# Controller.net
KiCad netlist of a schematic drawn in EAGLE
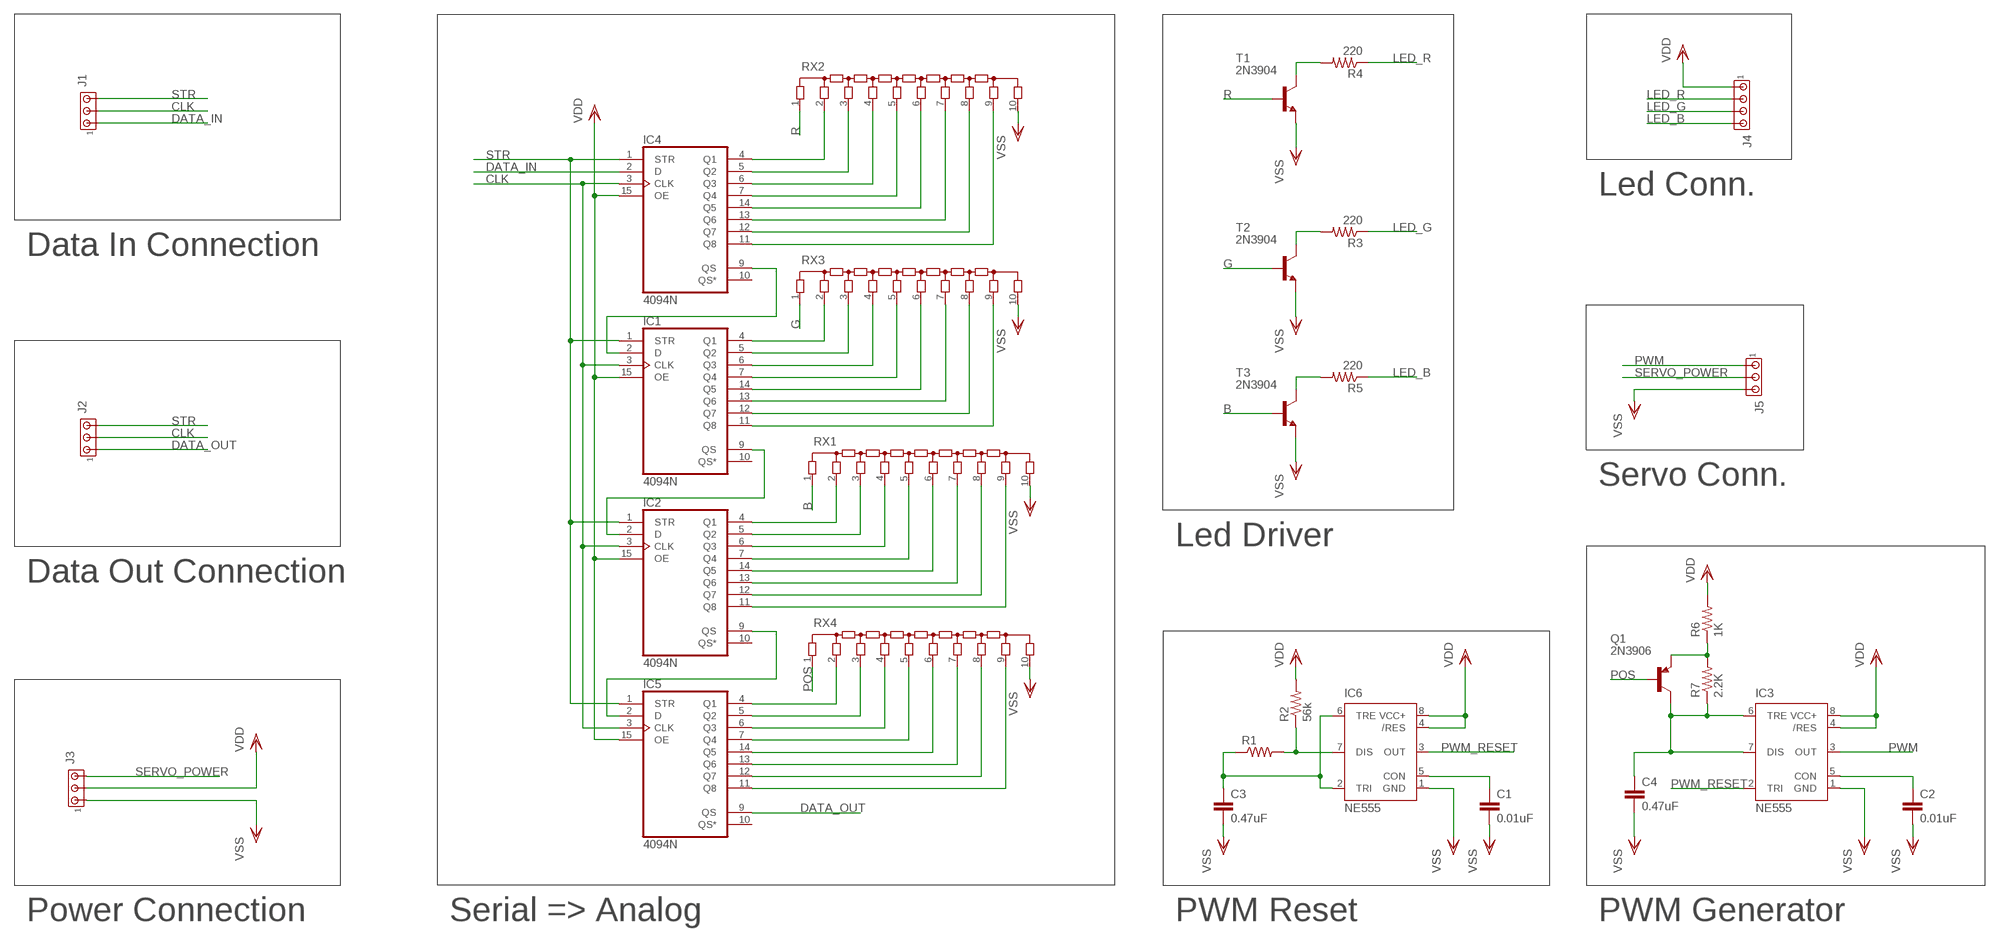
[diagram p0: schematic, sheet 1]

(export (version "E")
  (design (tool "Eeschema 10.0.6"))
  (components
    (comp (ref "C1")
      (value "0.01uF")
      (footprint "eagle-import:C5B2.5")
      (libsource (lib "eagle-import") (part "C5/2.5"))
    )
    (comp (ref "C2")
      (value "0.01uF")
      (footprint "eagle-import:C5B2.5")
      (libsource (lib "eagle-import") (part "C5/2.5"))
    )
    (comp (ref "C3")
      (value "0.47uF")
      (footprint "eagle-import:C5B2.5")
      (libsource (lib "eagle-import") (part "C5/2.5"))
    )
    (comp (ref "C4")
      (value "0.47uF")
      (footprint "eagle-import:C5B2.5")
      (libsource (lib "eagle-import") (part "C5/2.5"))
    )
    (comp (ref "IC1")
      (value "4094N")
      (footprint "eagle-import:DIL16")
      (libsource (lib "eagle-import") (part "4094N"))
    )
    (comp (ref "IC2")
      (value "4094N")
      (footprint "eagle-import:DIL16")
      (libsource (lib "eagle-import") (part "4094N"))
    )
    (comp (ref "IC3")
      (value "NE555")
      (footprint "eagle-import:DIL-08")
      (fields (field (name "MF") "Arrow Electronics") (field (name "MPN") "NE555N"))
      (libsource (lib "eagle-import") (part "NE555"))
    )
    (comp (ref "IC4")
      (value "4094N")
      (footprint "eagle-import:DIL16")
      (libsource (lib "eagle-import") (part "4094N"))
    )
    (comp (ref "IC5")
      (value "4094N")
      (footprint "eagle-import:DIL16")
      (libsource (lib "eagle-import") (part "4094N"))
    )
    (comp (ref "IC6")
      (value "NE555")
      (footprint "eagle-import:DIL-08")
      (fields (field (name "MF") "Arrow Electronics") (field (name "MPN") "NE555N"))
      (libsource (lib "eagle-import") (part "NE555"))
    )
    (comp (ref "J1")
      (value "MTA03-100")
      (footprint "eagle-import:10X03MTA")
      (libsource (lib "eagle-import") (part "MTA03-100"))
    )
    (comp (ref "J2")
      (value "MTA03-100")
      (footprint "eagle-import:10X03MTA")
      (libsource (lib "eagle-import") (part "MTA03-100"))
    )
    (comp (ref "J3")
      (value "MTA03-100")
      (footprint "eagle-import:10X03MTA")
      (libsource (lib "eagle-import") (part "MTA03-100"))
    )
    (comp (ref "J4")
      (value "MTA04-100")
      (footprint "eagle-import:10X04MTA")
      (libsource (lib "eagle-import") (part "MTA04-100"))
    )
    (comp (ref "J5")
      (value "MTA03-100")
      (footprint "eagle-import:10X03MTA")
      (libsource (lib "eagle-import") (part "MTA03-100"))
    )
    (comp (ref "Q1")
      (value "2N3906")
      (footprint "eagle-import:TO92")
      (libsource (lib "eagle-import") (part "2N3906"))
    )
    (comp (ref "R1")
      (value "R-US_0207/7")
      (footprint "eagle-import:0207_7")
      (libsource (lib "eagle-import") (part "R-US_0207/7"))
    )
    (comp (ref "R2")
      (value "56k")
      (footprint "eagle-import:0207_7")
      (libsource (lib "eagle-import") (part "R-US_0207/7"))
    )
    (comp (ref "R3")
      (value "220")
      (footprint "eagle-import:0207_7")
      (libsource (lib "eagle-import") (part "R-US_0207/7"))
    )
    (comp (ref "R4")
      (value "220")
      (footprint "eagle-import:0207_7")
      (libsource (lib "eagle-import") (part "R-US_0207/7"))
    )
    (comp (ref "R5")
      (value "220")
      (footprint "eagle-import:0207_7")
      (libsource (lib "eagle-import") (part "R-US_0207/7"))
    )
    (comp (ref "R6")
      (value "1K")
      (footprint "eagle-import:0207_7")
      (libsource (lib "eagle-import") (part "R-US_0207/7"))
    )
    (comp (ref "R7")
      (value "2.2K")
      (footprint "eagle-import:0207_7")
      (libsource (lib "eagle-import") (part "R-US_0207/7"))
    )
    (comp (ref "RX1")
      (value "R/2R-8")
      (footprint "eagle-import:SIL10")
      (libsource (lib "eagle-import") (part "R/2R-8"))
    )
    (comp (ref "RX2")
      (value "R/2R-8")
      (footprint "eagle-import:SIL10")
      (libsource (lib "eagle-import") (part "R/2R-8"))
    )
    (comp (ref "RX3")
      (value "R/2R-8")
      (footprint "eagle-import:SIL10")
      (libsource (lib "eagle-import") (part "R/2R-8"))
    )
    (comp (ref "RX4")
      (value "R/2R-8")
      (footprint "eagle-import:SIL10")
      (libsource (lib "eagle-import") (part "R/2R-8"))
    )
    (comp (ref "T1")
      (value "2N3904")
      (footprint "eagle-import:TO92")
      (libsource (lib "eagle-import") (part "2N3904"))
    )
    (comp (ref "T2")
      (value "2N3904")
      (footprint "eagle-import:TO92")
      (libsource (lib "eagle-import") (part "2N3904"))
    )
    (comp (ref "T3")
      (value "2N3904")
      (footprint "eagle-import:TO92")
      (libsource (lib "eagle-import") (part "2N3904"))
    )
  )
  (nets
    (net (code "1") (name "/B") (class "Default")
      (node (ref "RX1") (pin "1") (pinfunction "IN_1") (pintype "passive"))
      (node (ref "T3") (pin "2") (pinfunction "B_2") (pintype "passive"))
    )
    (net (code "2") (name "/CLK") (class "Default")
      (node (ref "IC1") (pin "3") (pinfunction "CLK_3") (pintype "input"))
      (node (ref "IC2") (pin "3") (pinfunction "CLK_3") (pintype "input"))
      (node (ref "IC4") (pin "3") (pinfunction "CLK_3") (pintype "input"))
      (node (ref "IC5") (pin "3") (pinfunction "CLK_3") (pintype "input"))
      (node (ref "J1") (pin "2") (pinfunction "2_2") (pintype "passive"))
      (node (ref "J2") (pin "2") (pinfunction "2_2") (pintype "passive"))
    )
    (net (code "3") (name "/DATA_IN") (class "Default")
      (node (ref "IC4") (pin "2") (pinfunction "D_2") (pintype "input"))
      (node (ref "J1") (pin "1") (pinfunction "1_1") (pintype "passive"))
    )
    (net (code "4") (name "/DATA_OUT") (class "Default")
      (node (ref "IC5") (pin "9") (pinfunction "QS_9") (pintype "output"))
      (node (ref "J2") (pin "1") (pinfunction "1_1") (pintype "passive"))
    )
    (net (code "5") (name "/G") (class "Default")
      (node (ref "RX3") (pin "1") (pinfunction "IN_1") (pintype "passive"))
      (node (ref "T2") (pin "2") (pinfunction "B_2") (pintype "passive"))
    )
    (net (code "6") (name "/LED_B") (class "Default")
      (node (ref "J4") (pin "4") (pinfunction "4_4") (pintype "passive"))
      (node (ref "R5") (pin "1") (pinfunction "1_1") (pintype "passive"))
    )
    (net (code "7") (name "/LED_G") (class "Default")
      (node (ref "J4") (pin "3") (pinfunction "3_3") (pintype "passive"))
      (node (ref "R3") (pin "1") (pinfunction "1_1") (pintype "passive"))
    )
    (net (code "8") (name "/LED_R") (class "Default")
      (node (ref "J4") (pin "2") (pinfunction "2_2") (pintype "passive"))
      (node (ref "R4") (pin "1") (pinfunction "1_1") (pintype "passive"))
    )
    (net (code "9") (name "/POS") (class "Default")
      (node (ref "Q1") (pin "2") (pinfunction "B_2") (pintype "passive"))
      (node (ref "RX4") (pin "1") (pinfunction "IN_1") (pintype "passive"))
    )
    (net (code "10") (name "/PWM") (class "Default")
      (node (ref "IC3") (pin "3") (pinfunction "OUT_3") (pintype "output"))
      (node (ref "J5") (pin "1") (pinfunction "1_1") (pintype "passive"))
    )
    (net (code "11") (name "/PWM_RESET") (class "Default")
      (node (ref "IC3") (pin "2") (pinfunction "TRI_2") (pintype "input"))
      (node (ref "IC6") (pin "3") (pinfunction "OUT_3") (pintype "output"))
    )
    (net (code "12") (name "/R") (class "Default")
      (node (ref "RX2") (pin "1") (pinfunction "IN_1") (pintype "passive"))
      (node (ref "T1") (pin "2") (pinfunction "B_2") (pintype "passive"))
    )
    (net (code "13") (name "/SERVO_POWER") (class "Default")
      (node (ref "J3") (pin "3") (pinfunction "3_3") (pintype "passive"))
      (node (ref "J5") (pin "2") (pinfunction "2_2") (pintype "passive"))
    )
    (net (code "14") (name "/STR") (class "Default")
      (node (ref "IC1") (pin "1") (pinfunction "STR_1") (pintype "input"))
      (node (ref "IC2") (pin "1") (pinfunction "STR_1") (pintype "input"))
      (node (ref "IC4") (pin "1") (pinfunction "STR_1") (pintype "input"))
      (node (ref "IC5") (pin "1") (pinfunction "STR_1") (pintype "input"))
      (node (ref "J1") (pin "3") (pinfunction "3_3") (pintype "passive"))
      (node (ref "J2") (pin "3") (pinfunction "3_3") (pintype "passive"))
    )
    (net (code "15") (name "Net-(IC1A-D)") (class "Default")
      (node (ref "IC1") (pin "2") (pinfunction "D_2") (pintype "input"))
      (node (ref "IC4") (pin "9") (pinfunction "QS_9") (pintype "output"))
    )
    (net (code "16") (name "Net-(IC1A-Q1)") (class "Default")
      (node (ref "IC1") (pin "4") (pinfunction "Q1_4") (pintype "output"))
      (node (ref "RX3") (pin "2") (pinfunction "B8_2") (pintype "passive"))
    )
    (net (code "17") (name "Net-(IC1A-Q2)") (class "Default")
      (node (ref "IC1") (pin "5") (pinfunction "Q2_5") (pintype "output"))
      (node (ref "RX3") (pin "3") (pinfunction "B7_3") (pintype "passive"))
    )
    (net (code "18") (name "Net-(IC1A-Q3)") (class "Default")
      (node (ref "IC1") (pin "6") (pinfunction "Q3_6") (pintype "output"))
      (node (ref "RX3") (pin "4") (pinfunction "B6_4") (pintype "passive"))
    )
    (net (code "19") (name "Net-(IC1A-Q4)") (class "Default")
      (node (ref "IC1") (pin "7") (pinfunction "Q4_7") (pintype "output"))
      (node (ref "RX3") (pin "5") (pinfunction "B5_5") (pintype "passive"))
    )
    (net (code "20") (name "Net-(IC1A-Q5)") (class "Default")
      (node (ref "IC1") (pin "14") (pinfunction "Q5_14") (pintype "output"))
      (node (ref "RX3") (pin "6") (pinfunction "B4_6") (pintype "passive"))
    )
    (net (code "21") (name "Net-(IC1A-Q6)") (class "Default")
      (node (ref "IC1") (pin "13") (pinfunction "Q6_13") (pintype "output"))
      (node (ref "RX3") (pin "7") (pinfunction "B3_7") (pintype "passive"))
    )
    (net (code "22") (name "Net-(IC1A-Q7)") (class "Default")
      (node (ref "IC1") (pin "12") (pinfunction "Q7_12") (pintype "output"))
      (node (ref "RX3") (pin "8") (pinfunction "B2_8") (pintype "passive"))
    )
    (net (code "23") (name "Net-(IC1A-Q8)") (class "Default")
      (node (ref "IC1") (pin "11") (pinfunction "Q8_11") (pintype "output"))
      (node (ref "RX3") (pin "9") (pinfunction "B1_9") (pintype "passive"))
    )
    (net (code "24") (name "Net-(IC1A-QS)") (class "Default")
      (node (ref "IC1") (pin "9") (pinfunction "QS_9") (pintype "output"))
      (node (ref "IC2") (pin "2") (pinfunction "D_2") (pintype "input"))
    )
    (net (code "25") (name "Net-(IC2A-Q1)") (class "Default")
      (node (ref "IC2") (pin "4") (pinfunction "Q1_4") (pintype "output"))
      (node (ref "RX1") (pin "2") (pinfunction "B8_2") (pintype "passive"))
    )
    (net (code "26") (name "Net-(IC2A-Q2)") (class "Default")
      (node (ref "IC2") (pin "5") (pinfunction "Q2_5") (pintype "output"))
      (node (ref "RX1") (pin "3") (pinfunction "B7_3") (pintype "passive"))
    )
    (net (code "27") (name "Net-(IC2A-Q3)") (class "Default")
      (node (ref "IC2") (pin "6") (pinfunction "Q3_6") (pintype "output"))
      (node (ref "RX1") (pin "4") (pinfunction "B6_4") (pintype "passive"))
    )
    (net (code "28") (name "Net-(IC2A-Q4)") (class "Default")
      (node (ref "IC2") (pin "7") (pinfunction "Q4_7") (pintype "output"))
      (node (ref "RX1") (pin "5") (pinfunction "B5_5") (pintype "passive"))
    )
    (net (code "29") (name "Net-(IC2A-Q5)") (class "Default")
      (node (ref "IC2") (pin "14") (pinfunction "Q5_14") (pintype "output"))
      (node (ref "RX1") (pin "6") (pinfunction "B4_6") (pintype "passive"))
    )
    (net (code "30") (name "Net-(IC2A-Q6)") (class "Default")
      (node (ref "IC2") (pin "13") (pinfunction "Q6_13") (pintype "output"))
      (node (ref "RX1") (pin "7") (pinfunction "B3_7") (pintype "passive"))
    )
    (net (code "31") (name "Net-(IC2A-Q7)") (class "Default")
      (node (ref "IC2") (pin "12") (pinfunction "Q7_12") (pintype "output"))
      (node (ref "RX1") (pin "8") (pinfunction "B2_8") (pintype "passive"))
    )
    (net (code "32") (name "Net-(IC2A-Q8)") (class "Default")
      (node (ref "IC2") (pin "11") (pinfunction "Q8_11") (pintype "output"))
      (node (ref "RX1") (pin "9") (pinfunction "B1_9") (pintype "passive"))
    )
    (net (code "33") (name "Net-(IC2A-QS)") (class "Default")
      (node (ref "IC2") (pin "9") (pinfunction "QS_9") (pintype "output"))
      (node (ref "IC5") (pin "2") (pinfunction "D_2") (pintype "input"))
    )
    (net (code "34") (name "Net-(IC3-CON)") (class "Default")
      (node (ref "C2") (pin "1") (pinfunction "1_1") (pintype "passive"))
      (node (ref "IC3") (pin "5") (pinfunction "CON_5") (pintype "input"))
    )
    (net (code "35") (name "Net-(IC3-DIS)") (class "Default")
      (node (ref "C4") (pin "1") (pinfunction "1_1") (pintype "passive"))
      (node (ref "IC3") (pin "6") (pinfunction "TRE_6") (pintype "input"))
      (node (ref "IC3") (pin "7") (pinfunction "DIS_7") (pintype "input"))
      (node (ref "Q1") (pin "1") (pinfunction "C_1") (pintype "passive"))
      (node (ref "R7") (pin "1") (pinfunction "1_1") (pintype "passive"))
    )
    (net (code "36") (name "Net-(IC4A-Q1)") (class "Default")
      (node (ref "IC4") (pin "4") (pinfunction "Q1_4") (pintype "output"))
      (node (ref "RX2") (pin "2") (pinfunction "B8_2") (pintype "passive"))
    )
    (net (code "37") (name "Net-(IC4A-Q2)") (class "Default")
      (node (ref "IC4") (pin "5") (pinfunction "Q2_5") (pintype "output"))
      (node (ref "RX2") (pin "3") (pinfunction "B7_3") (pintype "passive"))
    )
    (net (code "38") (name "Net-(IC4A-Q3)") (class "Default")
      (node (ref "IC4") (pin "6") (pinfunction "Q3_6") (pintype "output"))
      (node (ref "RX2") (pin "4") (pinfunction "B6_4") (pintype "passive"))
    )
    (net (code "39") (name "Net-(IC4A-Q4)") (class "Default")
      (node (ref "IC4") (pin "7") (pinfunction "Q4_7") (pintype "output"))
      (node (ref "RX2") (pin "5") (pinfunction "B5_5") (pintype "passive"))
    )
    (net (code "40") (name "Net-(IC4A-Q5)") (class "Default")
      (node (ref "IC4") (pin "14") (pinfunction "Q5_14") (pintype "output"))
      (node (ref "RX2") (pin "6") (pinfunction "B4_6") (pintype "passive"))
    )
    (net (code "41") (name "Net-(IC4A-Q6)") (class "Default")
      (node (ref "IC4") (pin "13") (pinfunction "Q6_13") (pintype "output"))
      (node (ref "RX2") (pin "7") (pinfunction "B3_7") (pintype "passive"))
    )
    (net (code "42") (name "Net-(IC4A-Q7)") (class "Default")
      (node (ref "IC4") (pin "12") (pinfunction "Q7_12") (pintype "output"))
      (node (ref "RX2") (pin "8") (pinfunction "B2_8") (pintype "passive"))
    )
    (net (code "43") (name "Net-(IC4A-Q8)") (class "Default")
      (node (ref "IC4") (pin "11") (pinfunction "Q8_11") (pintype "output"))
      (node (ref "RX2") (pin "9") (pinfunction "B1_9") (pintype "passive"))
    )
    (net (code "44") (name "Net-(IC5A-Q1)") (class "Default")
      (node (ref "IC5") (pin "4") (pinfunction "Q1_4") (pintype "output"))
      (node (ref "RX4") (pin "2") (pinfunction "B8_2") (pintype "passive"))
    )
    (net (code "45") (name "Net-(IC5A-Q2)") (class "Default")
      (node (ref "IC5") (pin "5") (pinfunction "Q2_5") (pintype "output"))
      (node (ref "RX4") (pin "3") (pinfunction "B7_3") (pintype "passive"))
    )
    (net (code "46") (name "Net-(IC5A-Q3)") (class "Default")
      (node (ref "IC5") (pin "6") (pinfunction "Q3_6") (pintype "output"))
      (node (ref "RX4") (pin "4") (pinfunction "B6_4") (pintype "passive"))
    )
    (net (code "47") (name "Net-(IC5A-Q4)") (class "Default")
      (node (ref "IC5") (pin "7") (pinfunction "Q4_7") (pintype "output"))
      (node (ref "RX4") (pin "5") (pinfunction "B5_5") (pintype "passive"))
    )
    (net (code "48") (name "Net-(IC5A-Q5)") (class "Default")
      (node (ref "IC5") (pin "14") (pinfunction "Q5_14") (pintype "output"))
      (node (ref "RX4") (pin "6") (pinfunction "B4_6") (pintype "passive"))
    )
    (net (code "49") (name "Net-(IC5A-Q6)") (class "Default")
      (node (ref "IC5") (pin "13") (pinfunction "Q6_13") (pintype "output"))
      (node (ref "RX4") (pin "7") (pinfunction "B3_7") (pintype "passive"))
    )
    (net (code "50") (name "Net-(IC5A-Q7)") (class "Default")
      (node (ref "IC5") (pin "12") (pinfunction "Q7_12") (pintype "output"))
      (node (ref "RX4") (pin "8") (pinfunction "B2_8") (pintype "passive"))
    )
    (net (code "51") (name "Net-(IC5A-Q8)") (class "Default")
      (node (ref "IC5") (pin "11") (pinfunction "Q8_11") (pintype "output"))
      (node (ref "RX4") (pin "9") (pinfunction "B1_9") (pintype "passive"))
    )
    (net (code "52") (name "Net-(IC6-CON)") (class "Default")
      (node (ref "C1") (pin "1") (pinfunction "1_1") (pintype "passive"))
      (node (ref "IC6") (pin "5") (pinfunction "CON_5") (pintype "input"))
    )
    (net (code "53") (name "Net-(IC6-DIS)") (class "Default")
      (node (ref "IC6") (pin "7") (pinfunction "DIS_7") (pintype "input"))
      (node (ref "R1") (pin "2") (pinfunction "2_2") (pintype "passive"))
      (node (ref "R2") (pin "1") (pinfunction "1_1") (pintype "passive"))
    )
    (net (code "54") (name "Net-(IC6-TRE)") (class "Default")
      (node (ref "C3") (pin "1") (pinfunction "1_1") (pintype "passive"))
      (node (ref "IC6") (pin "2") (pinfunction "TRI_2") (pintype "input"))
      (node (ref "IC6") (pin "6") (pinfunction "TRE_6") (pintype "input"))
      (node (ref "R1") (pin "1") (pinfunction "1_1") (pintype "passive"))
    )
    (net (code "55") (name "Net-(Q1-E)") (class "Default")
      (node (ref "Q1") (pin "3") (pinfunction "E_3") (pintype "passive"))
      (node (ref "R6") (pin "1") (pinfunction "1_1") (pintype "passive"))
      (node (ref "R7") (pin "2") (pinfunction "2_2") (pintype "passive"))
    )
    (net (code "56") (name "Net-(T1-C)") (class "Default")
      (node (ref "R4") (pin "2") (pinfunction "2_2") (pintype "passive"))
      (node (ref "T1") (pin "1") (pinfunction "C_1") (pintype "passive"))
    )
    (net (code "57") (name "Net-(T2-C)") (class "Default")
      (node (ref "R3") (pin "2") (pinfunction "2_2") (pintype "passive"))
      (node (ref "T2") (pin "1") (pinfunction "C_1") (pintype "passive"))
    )
    (net (code "58") (name "Net-(T3-C)") (class "Default")
      (node (ref "R5") (pin "2") (pinfunction "2_2") (pintype "passive"))
      (node (ref "T3") (pin "1") (pinfunction "C_1") (pintype "passive"))
    )
    (net (code "59") (name "VDD") (class "Default")
      (node (ref "IC1") (pin "15") (pinfunction "OE_15") (pintype "input"))
      (node (ref "IC2") (pin "15") (pinfunction "OE_15") (pintype "input"))
      (node (ref "IC3") (pin "4") (pinfunction "/RES_4") (pintype "input"))
      (node (ref "IC3") (pin "8") (pinfunction "VCC+_8") (pintype "power_in"))
      (node (ref "IC4") (pin "15") (pinfunction "OE_15") (pintype "input"))
      (node (ref "IC5") (pin "15") (pinfunction "OE_15") (pintype "input"))
      (node (ref "IC6") (pin "4") (pinfunction "/RES_4") (pintype "input"))
      (node (ref "IC6") (pin "8") (pinfunction "VCC+_8") (pintype "power_in"))
      (node (ref "J3") (pin "2") (pinfunction "2_2") (pintype "passive"))
      (node (ref "J4") (pin "1") (pinfunction "1_1") (pintype "passive"))
      (node (ref "R2") (pin "2") (pinfunction "2_2") (pintype "passive"))
      (node (ref "R6") (pin "2") (pinfunction "2_2") (pintype "passive"))
    )
    (net (code "60") (name "VSS") (class "Default")
      (node (ref "C1") (pin "2") (pinfunction "2_2") (pintype "passive"))
      (node (ref "C2") (pin "2") (pinfunction "2_2") (pintype "passive"))
      (node (ref "C3") (pin "2") (pinfunction "2_2") (pintype "passive"))
      (node (ref "C4") (pin "2") (pinfunction "2_2") (pintype "passive"))
      (node (ref "IC3") (pin "1") (pinfunction "GND_1") (pintype "power_in"))
      (node (ref "IC6") (pin "1") (pinfunction "GND_1") (pintype "power_in"))
      (node (ref "J3") (pin "1") (pinfunction "1_1") (pintype "passive"))
      (node (ref "J5") (pin "3") (pinfunction "3_3") (pintype "passive"))
      (node (ref "RX1") (pin "10") (pinfunction "OUT_10") (pintype "passive"))
      (node (ref "RX2") (pin "10") (pinfunction "OUT_10") (pintype "passive"))
      (node (ref "RX3") (pin "10") (pinfunction "OUT_10") (pintype "passive"))
      (node (ref "RX4") (pin "10") (pinfunction "OUT_10") (pintype "passive"))
      (node (ref "T1") (pin "3") (pinfunction "E_3") (pintype "passive"))
      (node (ref "T2") (pin "3") (pinfunction "E_3") (pintype "passive"))
      (node (ref "T3") (pin "3") (pinfunction "E_3") (pintype "passive"))
    )
    (net (code "61") (name "unconnected-(IC1A-QS*-Pad10)") (class "Default")
      (node (ref "IC1") (pin "10") (pinfunction "QS*_10") (pintype "output"))
    )
    (net (code "62") (name "unconnected-(IC2A-QS*-Pad10)") (class "Default")
      (node (ref "IC2") (pin "10") (pinfunction "QS*_10") (pintype "output"))
    )
    (net (code "63") (name "unconnected-(IC4A-QS*-Pad10)") (class "Default")
      (node (ref "IC4") (pin "10") (pinfunction "QS*_10") (pintype "output"))
    )
    (net (code "64") (name "unconnected-(IC5A-QS*-Pad10)") (class "Default")
      (node (ref "IC5") (pin "10") (pinfunction "QS*_10") (pintype "output"))
    )
  )
)
